# io.net
KiCad netlist of a schematic drawn in EAGLE
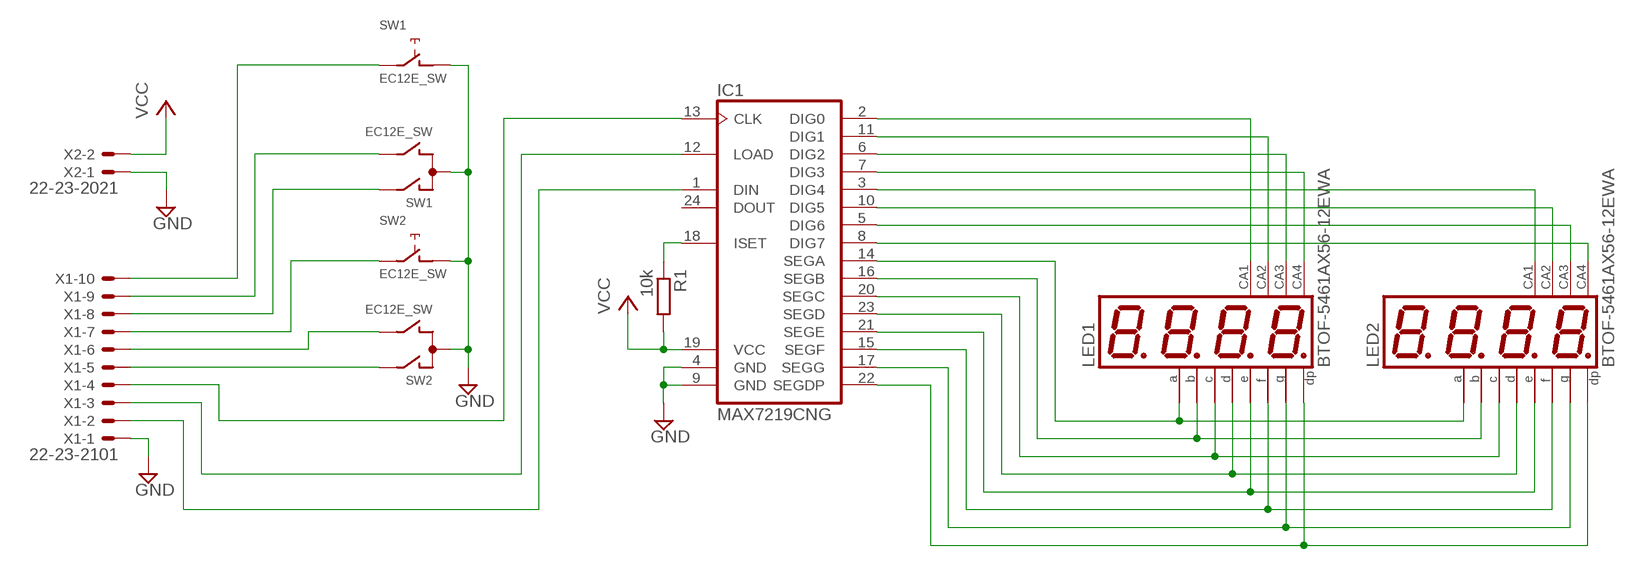
[diagram p0: schematic, sheet 1]

(export (version "E")
  (design (tool "Eeschema 10.0.6"))
  (components
    (comp (ref "IC1")
      (value "MAX7219CNG")
      (footprint "eagle-import:DIL24-3")
      (fields (field (name "MF") "MAXIM"))
      (libsource (lib "eagle-import") (part "MAX7219CNG"))
    )
    (comp (ref "LED1")
      (value "BTOF-5461AX56-12EWA")
      (footprint "eagle-import:BX56-12")
      (libsource (lib "eagle-import") (part "B?56-12WATOF-5461AXE"))
    )
    (comp (ref "LED2")
      (value "BTOF-5461AX56-12EWA")
      (footprint "eagle-import:BX56-12")
      (libsource (lib "eagle-import") (part "B?56-12WATOF-5461AXE"))
    )
    (comp (ref "R1")
      (value "10k")
      (footprint "eagle-import:0207_10")
      (libsource (lib "eagle-import") (part "R-EU_0207/10"))
    )
    (comp (ref "SW1")
      (value "EC12E_SW")
      (footprint "eagle-import:ALPS_EC12E_SW")
      (fields (field (name "MPN") "EC12E2424407"))
      (libsource (lib "eagle-import") (part "EC12E_SW"))
    )
    (comp (ref "SW2")
      (value "EC12E_SW")
      (footprint "eagle-import:ALPS_EC12E_SW")
      (fields (field (name "MPN") "EC12E2424407"))
      (libsource (lib "eagle-import") (part "EC12E_SW"))
    )
    (comp (ref "X1")
      (value "22-23-2101")
      (footprint "eagle-import:22-23-2101")
      (fields (field (name "MF") "MOLEX"))
      (libsource (lib "eagle-import") (part "22-23-2101"))
    )
    (comp (ref "X2")
      (value "22-23-2021")
      (footprint "eagle-import:22-23-2021")
      (fields (field (name "MF") "MOLEX"))
      (libsource (lib "eagle-import") (part "22-23-2021"))
    )
  )
  (nets
    (net (code "1") (name "GND") (class "Default")
      (node (ref "IC1") (pin "4") (pinfunction "GND_4") (pintype "power_in"))
      (node (ref "IC1") (pin "9") (pinfunction "GND_9") (pintype "power_in"))
      (node (ref "SW1") (pin "C") (pinfunction "C_C") (pintype "passive"))
      (node (ref "SW1") (pin "D") (pinfunction "1_D") (pintype "passive"))
      (node (ref "SW2") (pin "C") (pinfunction "C_C") (pintype "passive"))
      (node (ref "SW2") (pin "D") (pinfunction "1_D") (pintype "passive"))
      (node (ref "X1") (pin "1") (pinfunction "S_1") (pintype "passive"))
      (node (ref "X2") (pin "1") (pinfunction "S_1") (pintype "passive"))
    )
    (net (code "2") (name "Net-(IC1-CLK)") (class "Default")
      (node (ref "IC1") (pin "13") (pinfunction "CLK_13") (pintype "input"))
      (node (ref "X1") (pin "4") (pinfunction "S_4") (pintype "passive"))
    )
    (net (code "3") (name "Net-(IC1-DIG0)") (class "Default")
      (node (ref "IC1") (pin "2") (pinfunction "DIG0_2") (pintype "output"))
      (node (ref "LED1") (pin "12") (pinfunction "CA_12") (pintype "passive"))
    )
    (net (code "4") (name "Net-(IC1-DIG1)") (class "Default")
      (node (ref "IC1") (pin "11") (pinfunction "DIG1_11") (pintype "output"))
      (node (ref "LED1") (pin "9") (pinfunction "CA_9") (pintype "passive"))
    )
    (net (code "5") (name "Net-(IC1-DIG2)") (class "Default")
      (node (ref "IC1") (pin "6") (pinfunction "DIG2_6") (pintype "output"))
      (node (ref "LED1") (pin "8") (pinfunction "CA_8") (pintype "passive"))
    )
    (net (code "6") (name "Net-(IC1-DIG3)") (class "Default")
      (node (ref "IC1") (pin "7") (pinfunction "DIG3_7") (pintype "output"))
      (node (ref "LED1") (pin "6") (pinfunction "CA_6") (pintype "passive"))
    )
    (net (code "7") (name "Net-(IC1-DIG4)") (class "Default")
      (node (ref "IC1") (pin "3") (pinfunction "DIG4_3") (pintype "output"))
      (node (ref "LED2") (pin "12") (pinfunction "CA_12") (pintype "passive"))
    )
    (net (code "8") (name "Net-(IC1-DIG5)") (class "Default")
      (node (ref "IC1") (pin "10") (pinfunction "DIG5_10") (pintype "output"))
      (node (ref "LED2") (pin "9") (pinfunction "CA_9") (pintype "passive"))
    )
    (net (code "9") (name "Net-(IC1-DIG6)") (class "Default")
      (node (ref "IC1") (pin "5") (pinfunction "DIG6_5") (pintype "output"))
      (node (ref "LED2") (pin "8") (pinfunction "CA_8") (pintype "passive"))
    )
    (net (code "10") (name "Net-(IC1-DIG7)") (class "Default")
      (node (ref "IC1") (pin "8") (pinfunction "DIG7_8") (pintype "output"))
      (node (ref "LED2") (pin "6") (pinfunction "CA_6") (pintype "passive"))
    )
    (net (code "11") (name "Net-(IC1-DIN)") (class "Default")
      (node (ref "IC1") (pin "1") (pinfunction "DIN_1") (pintype "input"))
      (node (ref "X1") (pin "2") (pinfunction "S_2") (pintype "passive"))
    )
    (net (code "12") (name "Net-(IC1-ISET)") (class "Default")
      (node (ref "IC1") (pin "18") (pinfunction "ISET_18") (pintype "input"))
      (node (ref "R1") (pin "1") (pinfunction "1_1") (pintype "passive"))
    )
    (net (code "13") (name "Net-(IC1-LOAD)") (class "Default")
      (node (ref "IC1") (pin "12") (pinfunction "LOAD_12") (pintype "input"))
      (node (ref "X1") (pin "3") (pinfunction "S_3") (pintype "passive"))
    )
    (net (code "14") (name "Net-(IC1-SEGA)") (class "Default")
      (node (ref "IC1") (pin "14") (pinfunction "SEGA_14") (pintype "output"))
      (node (ref "LED1") (pin "11") (pinfunction "A_11") (pintype "passive"))
      (node (ref "LED2") (pin "11") (pinfunction "A_11") (pintype "passive"))
    )
    (net (code "15") (name "Net-(IC1-SEGB)") (class "Default")
      (node (ref "IC1") (pin "16") (pinfunction "SEGB_16") (pintype "output"))
      (node (ref "LED1") (pin "7") (pinfunction "B_7") (pintype "passive"))
      (node (ref "LED2") (pin "7") (pinfunction "B_7") (pintype "passive"))
    )
    (net (code "16") (name "Net-(IC1-SEGC)") (class "Default")
      (node (ref "IC1") (pin "20") (pinfunction "SEGC_20") (pintype "output"))
      (node (ref "LED1") (pin "4") (pinfunction "C_4") (pintype "passive"))
      (node (ref "LED2") (pin "4") (pinfunction "C_4") (pintype "passive"))
    )
    (net (code "17") (name "Net-(IC1-SEGD)") (class "Default")
      (node (ref "IC1") (pin "23") (pinfunction "SEGD_23") (pintype "output"))
      (node (ref "LED1") (pin "2") (pinfunction "D_2") (pintype "passive"))
      (node (ref "LED2") (pin "2") (pinfunction "D_2") (pintype "passive"))
    )
    (net (code "18") (name "Net-(IC1-SEGDP)") (class "Default")
      (node (ref "IC1") (pin "22") (pinfunction "SEGDP_22") (pintype "output"))
      (node (ref "LED1") (pin "3") (pinfunction "DP_3") (pintype "passive"))
      (node (ref "LED2") (pin "3") (pinfunction "DP_3") (pintype "passive"))
    )
    (net (code "19") (name "Net-(IC1-SEGE)") (class "Default")
      (node (ref "IC1") (pin "21") (pinfunction "SEGE_21") (pintype "output"))
      (node (ref "LED1") (pin "1") (pinfunction "E_1") (pintype "passive"))
      (node (ref "LED2") (pin "1") (pinfunction "E_1") (pintype "passive"))
    )
    (net (code "20") (name "Net-(IC1-SEGF)") (class "Default")
      (node (ref "IC1") (pin "15") (pinfunction "SEGF_15") (pintype "output"))
      (node (ref "LED1") (pin "10") (pinfunction "F_10") (pintype "passive"))
      (node (ref "LED2") (pin "10") (pinfunction "F_10") (pintype "passive"))
    )
    (net (code "21") (name "Net-(IC1-SEGG)") (class "Default")
      (node (ref "IC1") (pin "17") (pinfunction "SEGG_17") (pintype "output"))
      (node (ref "LED1") (pin "5") (pinfunction "G_5") (pintype "passive"))
      (node (ref "LED2") (pin "5") (pinfunction "G_5") (pintype "passive"))
    )
    (net (code "22") (name "Net-(SW1B-2)") (class "Default")
      (node (ref "SW1") (pin "E") (pinfunction "2_E") (pintype "passive"))
      (node (ref "X1") (pin "10") (pinfunction "S_10") (pintype "passive"))
    )
    (net (code "23") (name "Net-(SW2B-2)") (class "Default")
      (node (ref "SW2") (pin "E") (pinfunction "2_E") (pintype "passive"))
      (node (ref "X1") (pin "7") (pinfunction "S_7") (pintype "passive"))
    )
    (net (code "24") (name "Net-(X1F-S)") (class "Default")
      (node (ref "SW2") (pin "A") (pinfunction "A_A") (pintype "passive"))
      (node (ref "X1") (pin "5") (pinfunction "S_5") (pintype "passive"))
    )
    (net (code "25") (name "Net-(X1G-S)") (class "Default")
      (node (ref "SW2") (pin "B") (pinfunction "B_B") (pintype "passive"))
      (node (ref "X1") (pin "6") (pinfunction "S_6") (pintype "passive"))
    )
    (net (code "26") (name "Net-(X1I-S)") (class "Default")
      (node (ref "SW1") (pin "A") (pinfunction "A_A") (pintype "passive"))
      (node (ref "X1") (pin "8") (pinfunction "S_8") (pintype "passive"))
    )
    (net (code "27") (name "Net-(X1J-S)") (class "Default")
      (node (ref "SW1") (pin "B") (pinfunction "B_B") (pintype "passive"))
      (node (ref "X1") (pin "9") (pinfunction "S_9") (pintype "passive"))
    )
    (net (code "28") (name "VCC") (class "Default")
      (node (ref "IC1") (pin "19") (pinfunction "VCC_19") (pintype "power_in"))
      (node (ref "R1") (pin "2") (pinfunction "2_2") (pintype "passive"))
      (node (ref "X2") (pin "2") (pinfunction "S_2") (pintype "passive"))
    )
    (net (code "29") (name "unconnected-(IC1-DOUT-Pad24)") (class "Default")
      (node (ref "IC1") (pin "24") (pinfunction "DOUT_24") (pintype "output"))
    )
  )
)
